# MicroMod-Artemis-ProcessorBoard.net
KiCad netlist of a schematic drawn in EAGLE
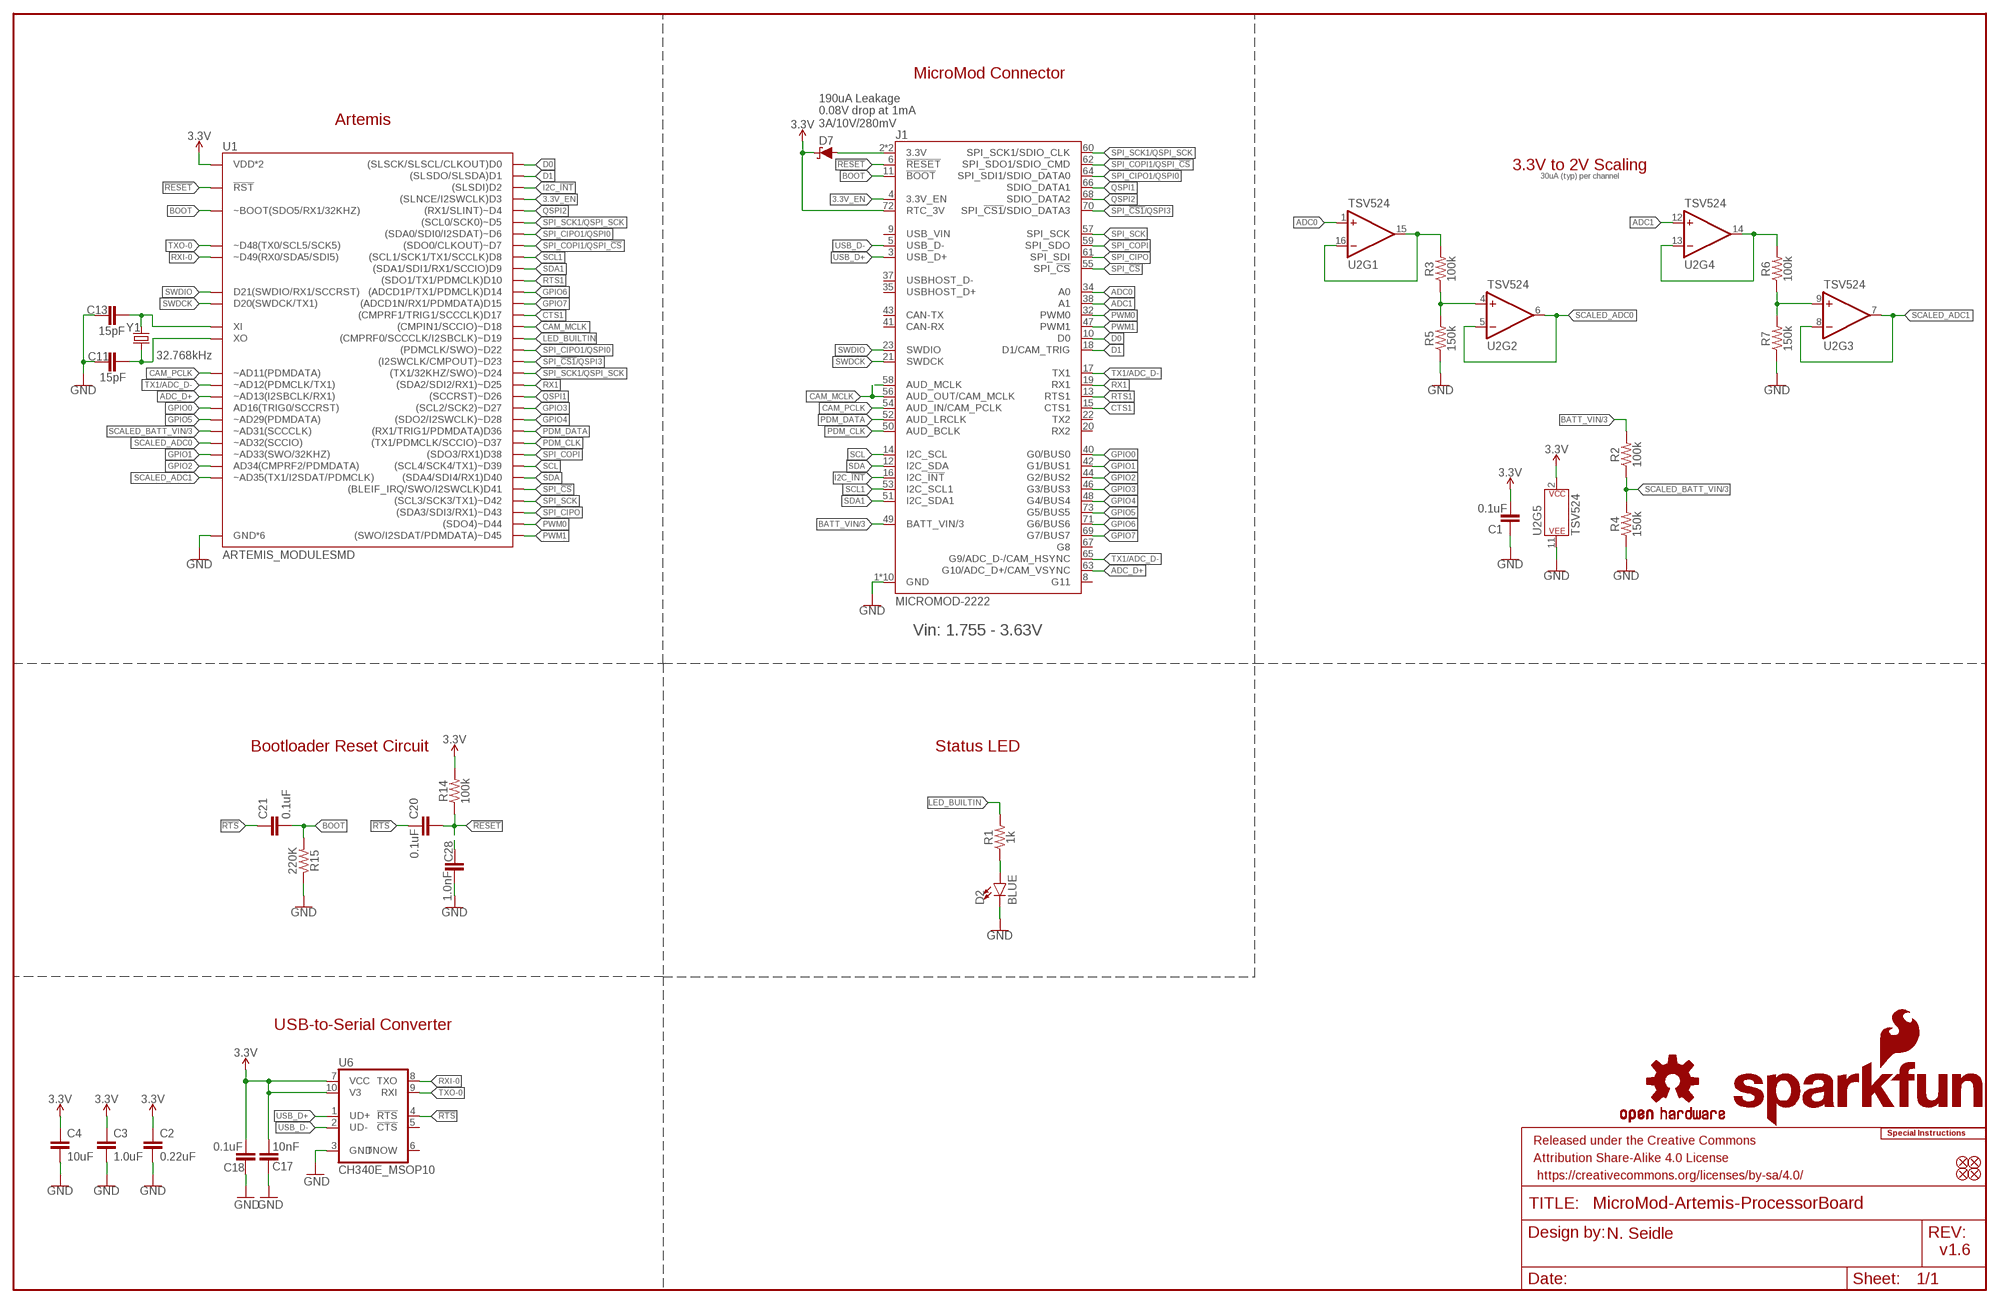
[diagram p0: schematic, sheet 1]

(export (version "E")
  (design (tool "Eeschema 10.0.6"))
  (components
    (comp (ref "C1")
      (value "0.1uF")
      (footprint "eagle-import:0402-TIGHT")
      (libsource (lib "eagle-import") (part "0.1UF-0402T-16V-10%"))
    )
    (comp (ref "C2")
      (value "0.22uF")
      (footprint "eagle-import:0402-TIGHT")
      (libsource (lib "eagle-import") (part "0.22UF-0402T-10V-10%"))
    )
    (comp (ref "C3")
      (value "1.0uF")
      (footprint "eagle-import:0402-TIGHT")
      (libsource (lib "eagle-import") (part "1.0UF-0402T-16V-10%"))
    )
    (comp (ref "C4")
      (value "10uF")
      (footprint "eagle-import:0603")
      (libsource (lib "eagle-import") (part "10UF-0603-6.3V-20%"))
    )
    (comp (ref "C11")
      (value "15pF")
      (footprint "eagle-import:0402-TIGHT")
      (libsource (lib "eagle-import") (part "15PF-0402T-50V-5%"))
    )
    (comp (ref "C13")
      (value "15pF")
      (footprint "eagle-import:0402-TIGHT")
      (libsource (lib "eagle-import") (part "15PF-0402T-50V-5%"))
    )
    (comp (ref "C17")
      (value "10nF")
      (footprint "eagle-import:0402-TIGHT")
      (libsource (lib "eagle-import") (part "10NF-0402T-25V-10%"))
    )
    (comp (ref "C18")
      (value "0.1uF")
      (footprint "eagle-import:0402-TIGHT")
      (libsource (lib "eagle-import") (part "0.1UF-0402T-16V-10%"))
    )
    (comp (ref "C20")
      (value "0.1uF")
      (footprint "eagle-import:0402-TIGHT")
      (libsource (lib "eagle-import") (part "0.1UF-0402T-16V-10%"))
    )
    (comp (ref "C21")
      (value "0.1uF")
      (footprint "eagle-import:0402-TIGHT")
      (libsource (lib "eagle-import") (part "0.1UF-0402T-16V-10%"))
    )
    (comp (ref "C28")
      (value "1.0nF")
      (footprint "eagle-import:0402-TIGHT")
      (libsource (lib "eagle-import") (part "1.0NF/1000PF-0402_TIGHT-50V-10%"))
    )
    (comp (ref "D2")
      (value "BLUE")
      (footprint "eagle-import:LED-0603")
      (libsource (lib "eagle-import") (part "LED-BLUE0603"))
    )
    (comp (ref "D7")
      (value "3A/10V/280mV")
      (footprint "eagle-import:SOD-323")
      (libsource (lib "eagle-import") (part "DIODE-SCHOTTKY-BAT60A"))
    )
    (comp (ref "FD1")
      (value "FIDUCIALUFIDUCIAL")
      (footprint "eagle-import:FIDUCIAL-MICRO")
      (libsource (lib "eagle-import") (part "FIDUCIALUFIDUCIAL"))
    )
    (comp (ref "FD2")
      (value "FIDUCIALUFIDUCIAL")
      (footprint "eagle-import:FIDUCIAL-MICRO")
      (libsource (lib "eagle-import") (part "FIDUCIALUFIDUCIAL"))
    )
    (comp (ref "FD3")
      (value "FIDUCIALUFIDUCIAL")
      (footprint "eagle-import:FIDUCIAL-MICRO")
      (libsource (lib "eagle-import") (part "FIDUCIALUFIDUCIAL"))
    )
    (comp (ref "FD4")
      (value "FIDUCIALUFIDUCIAL")
      (footprint "eagle-import:FIDUCIAL-MICRO")
      (libsource (lib "eagle-import") (part "FIDUCIALUFIDUCIAL"))
    )
    (comp (ref "FRAME1")
      (value "FRAME-LEDGER")
      (footprint "eagle-import:CREATIVE_COMMONS")
      (libsource (lib "eagle-import") (part "FRAME-LEDGER"))
    )
    (comp (ref "J1")
      (value "MICROMOD-2222")
      (footprint "eagle-import:M.2-CARD-E-22")
      (libsource (lib "eagle-import") (part "MICROMOD-2222"))
    )
    (comp (ref "LOGO1")
      (value "SFE_LOGO_NAME_FLAME.1_INCH")
      (footprint "eagle-import:SFE_LOGO_NAME_FLAME_.1")
      (libsource (lib "eagle-import") (part "SFE_LOGO_NAME_FLAME.1_INCH"))
    )
    (comp (ref "LOGO2")
      (value "SFE_LOGO_FLAME.1_INCH")
      (footprint "eagle-import:SFE_LOGO_FLAME_.1")
      (libsource (lib "eagle-import") (part "SFE_LOGO_FLAME.1_INCH"))
    )
    (comp (ref "LOGO3")
      (value "OSHW-LOGOMINI")
      (footprint "eagle-import:OSHW-LOGO-MINI")
      (libsource (lib "eagle-import") (part "OSHW-LOGOMINI"))
    )
    (comp (ref "LOGO4")
      (value "SPECIAL_INSTRUCTIONS-ORDERING")
      (footprint "eagle-import:ORDERING_INSTRUCTIONS")
      (libsource (lib "eagle-import") (part "SPECIAL_INSTRUCTIONS-ORDERING"))
    )
    (comp (ref "R1")
      (value "1k")
      (footprint "eagle-import:0402-TIGHT")
      (libsource (lib "eagle-import") (part "1KOHM-0402T-1/16W-1%"))
    )
    (comp (ref "R2")
      (value "100k")
      (footprint "eagle-import:0402-TIGHT")
      (libsource (lib "eagle-import") (part "100KOHM-0402T-1/16W-1%"))
    )
    (comp (ref "R3")
      (value "100k")
      (footprint "eagle-import:0402-TIGHT")
      (libsource (lib "eagle-import") (part "100KOHM-0402T-1/16W-1%"))
    )
    (comp (ref "R4")
      (value "150k")
      (footprint "eagle-import:0402-TIGHT")
      (libsource (lib "eagle-import") (part "150KOHM-0402T-1/16W-1%"))
    )
    (comp (ref "R5")
      (value "150k")
      (footprint "eagle-import:0402-TIGHT")
      (libsource (lib "eagle-import") (part "150KOHM-0402T-1/16W-1%"))
    )
    (comp (ref "R6")
      (value "100k")
      (footprint "eagle-import:0402-TIGHT")
      (libsource (lib "eagle-import") (part "100KOHM-0402T-1/16W-1%"))
    )
    (comp (ref "R7")
      (value "150k")
      (footprint "eagle-import:0402-TIGHT")
      (libsource (lib "eagle-import") (part "150KOHM-0402T-1/16W-1%"))
    )
    (comp (ref "R14")
      (value "100k")
      (footprint "eagle-import:0402-TIGHT")
      (libsource (lib "eagle-import") (part "100KOHM-0402T-1/16W-1%"))
    )
    (comp (ref "R15")
      (value "220K")
      (footprint "eagle-import:0402-TIGHT")
      (libsource (lib "eagle-import") (part "220KOHM-0402T-1/16W-1%"))
    )
    (comp (ref "U1")
      (value "ARTEMIS_MODULESMD")
      (footprint "eagle-import:ARTEMIS_FP")
      (libsource (lib "eagle-import") (part "ARTEMIS_MODULESMD"))
    )
    (comp (ref "U2")
      (value "TSV524")
      (footprint "eagle-import:QFN-16")
      (libsource (lib "eagle-import") (part "TSV524"))
    )
    (comp (ref "U6")
      (value "CH340E_MSOP10")
      (footprint "eagle-import:MSOP10")
      (libsource (lib "eagle-import") (part "CH340E_MSOP10"))
    )
    (comp (ref "Y1")
      (value "32.768kHz")
      (footprint "eagle-import:CRYSTAL-SMD-3.2X1.5MM")
      (libsource (lib "eagle-import") (part "CRYSTAL-32.768KHZSMD-3.2X1.5"))
    )
  )
  (nets
    (net (code "1") (name "/I2C_~{INT}") (class "Default")
      (node (ref "J1") (pin "16") (pinfunction "I2C_~{INT}_16") (pintype "bidirectional"))
      (node (ref "U1") (pin "D2") (pinfunction "(SLSDI)D2_D2") (pintype "bidirectional"))
    )
    (net (code "2") (name "/SPI_COPI1{slash}QSPI_~{CS}") (class "Default")
      (node (ref "J1") (pin "62") (pinfunction "SPI_SDO1/SDIO_CMD_62") (pintype "bidirectional"))
      (node (ref "U1") (pin "D7") (pinfunction "(SDO0/CLKOUT)~{D7}_D7") (pintype "bidirectional"))
    )
    (net (code "3") (name "/SPI_~{CS1}{slash}QSPI3") (class "Default")
      (node (ref "J1") (pin "70") (pinfunction "SPI_~{CS1}/SDIO_DATA3_70") (pintype "bidirectional"))
      (node (ref "U1") (pin "~D23") (pinfunction "(I2SWCLK/CMPOUT)~{D23}_~D23") (pintype "bidirectional"))
    )
    (net (code "4") (name "/SPI_~{CS}") (class "Default")
      (node (ref "J1") (pin "55") (pinfunction "SPI_~{CS}_55") (pintype "bidirectional"))
      (node (ref "U1") (pin "D41") (pinfunction "(BLEIF_IRQ/SWO/I2SWCLK)D41_D41") (pintype "bidirectional"))
    )
    (net (code "5") (name "/~{RESET}") (class "Default")
      (node (ref "C20") (pin "2") (pinfunction "2_2") (pintype "passive"))
      (node (ref "C28") (pin "1") (pinfunction "1_1") (pintype "passive"))
      (node (ref "J1") (pin "6") (pinfunction "~{RESET}_6") (pintype "bidirectional"))
      (node (ref "R14") (pin "1") (pinfunction "1_1") (pintype "passive"))
      (node (ref "U1") (pin "~RST") (pinfunction "~{RST}_~RST") (pintype "bidirectional"))
    )
    (net (code "6") (name "/~{RTS}") (class "Default")
      (node (ref "C20") (pin "1") (pinfunction "1_1") (pintype "passive"))
      (node (ref "C21") (pin "1") (pinfunction "1_1") (pintype "passive"))
      (node (ref "U6") (pin "4") (pinfunction "~{RTS}_4") (pintype "bidirectional"))
    )
    (net (code "7") (name "3.3V") (class "Default")
      (node (ref "C1") (pin "1") (pinfunction "1_1") (pintype "passive"))
      (node (ref "C17") (pin "1") (pinfunction "1_1") (pintype "passive"))
      (node (ref "C18") (pin "1") (pinfunction "1_1") (pintype "passive"))
      (node (ref "C2") (pin "1") (pinfunction "1_1") (pintype "passive"))
      (node (ref "C3") (pin "1") (pinfunction "1_1") (pintype "passive"))
      (node (ref "C4") (pin "1") (pinfunction "1_1") (pintype "passive"))
      (node (ref "D7") (pin "C") (pinfunction "C_C") (pintype "passive"))
      (node (ref "J1") (pin "72") (pinfunction "RTC_3V_72") (pintype "bidirectional"))
      (node (ref "R14") (pin "2") (pinfunction "2_2") (pintype "passive"))
      (node (ref "U1") (pin "VDD@36") (pinfunction "VDD*2_VDD@36") (pintype "bidirectional"))
      (node (ref "U1") (pin "VDD@37") (pinfunction "VDD*2_VDD@37") (pintype "bidirectional"))
      (node (ref "U2") (pin "2") (pinfunction "V+_2") (pintype "bidirectional"))
      (node (ref "U6") (pin "10") (pinfunction "V3_10") (pintype "bidirectional"))
      (node (ref "U6") (pin "7") (pinfunction "VCC_7") (pintype "bidirectional"))
    )
    (net (code "8") (name "3.3V_EN") (class "Default")
      (node (ref "J1") (pin "4") (pinfunction "3.3V_EN_4") (pintype "bidirectional"))
      (node (ref "U1") (pin "D3") (pinfunction "(SLNCE/I2SWCLK)D3_D3") (pintype "bidirectional"))
    )
    (net (code "9") (name "ADC0") (class "Default")
      (node (ref "J1") (pin "34") (pinfunction "A0_34") (pintype "bidirectional"))
      (node (ref "U2") (pin "1") (pinfunction "+IN_1") (pintype "input"))
    )
    (net (code "10") (name "ADC1") (class "Default")
      (node (ref "J1") (pin "38") (pinfunction "A1_38") (pintype "bidirectional"))
      (node (ref "U2") (pin "12") (pinfunction "+IN_12") (pintype "input"))
    )
    (net (code "11") (name "ADC_D+") (class "Default")
      (node (ref "J1") (pin "63") (pinfunction "G10/ADC_D+/CAM_VSYNC_63") (pintype "bidirectional"))
      (node (ref "U1") (pin "~AD13") (pinfunction "~{AD13(I2SBCLK/RX1})_~AD13") (pintype "bidirectional"))
    )
    (net (code "12") (name "BATT_VIN{slash}3") (class "Default")
      (node (ref "J1") (pin "49") (pinfunction "BATT_VIN/3_49") (pintype "bidirectional"))
      (node (ref "R2") (pin "2") (pinfunction "2_2") (pintype "passive"))
    )
    (net (code "13") (name "BOOT") (class "Default")
      (node (ref "C21") (pin "2") (pinfunction "2_2") (pintype "passive"))
      (node (ref "J1") (pin "11") (pinfunction "~{BOOT}_11") (pintype "bidirectional"))
      (node (ref "R15") (pin "2") (pinfunction "2_2") (pintype "passive"))
      (node (ref "U1") (pin "BOOT") (pinfunction "~{BOOT(SDO5/RX1/32KHZ})_BOOT") (pintype "bidirectional"))
    )
    (net (code "14") (name "CAM_MCLK") (class "Default")
      (node (ref "J1") (pin "56") (pinfunction "AUD_OUT/CAM_MCLK_56") (pintype "bidirectional"))
      (node (ref "J1") (pin "58") (pinfunction "AUD_MCLK_58") (pintype "bidirectional"))
      (node (ref "U1") (pin "~D18") (pinfunction "(CMPIN1/SCCIO)~{D18}_~D18") (pintype "bidirectional"))
    )
    (net (code "15") (name "CAM_PCLK") (class "Default")
      (node (ref "J1") (pin "54") (pinfunction "AUD_IN/CAM_PCLK_54") (pintype "bidirectional"))
      (node (ref "U1") (pin "~AD11") (pinfunction "~{AD11(PDMDATA})_~AD11") (pintype "bidirectional"))
    )
    (net (code "16") (name "CTS1") (class "Default")
      (node (ref "J1") (pin "15") (pinfunction "CTS1_15") (pintype "bidirectional"))
      (node (ref "U1") (pin "D17") (pinfunction "(CMPRF1/TRIG1/SCCCLK)D17_D17") (pintype "bidirectional"))
    )
    (net (code "17") (name "D0") (class "Default")
      (node (ref "J1") (pin "10") (pinfunction "D0_10") (pintype "bidirectional"))
      (node (ref "U1") (pin "D0") (pinfunction "(SLSCK/SLSCL/CLKOUT)D0_D0") (pintype "bidirectional"))
    )
    (net (code "18") (name "D1") (class "Default")
      (node (ref "J1") (pin "18") (pinfunction "D1/CAM_TRIG_18") (pintype "bidirectional"))
      (node (ref "U1") (pin "D1") (pinfunction "(SLSDO/SLSDA)D1_D1") (pintype "bidirectional"))
    )
    (net (code "19") (name "GND") (class "Default")
      (node (ref "C1") (pin "2") (pinfunction "2_2") (pintype "passive"))
      (node (ref "C11") (pin "1") (pinfunction "1_1") (pintype "passive"))
      (node (ref "C13") (pin "1") (pinfunction "1_1") (pintype "passive"))
      (node (ref "C17") (pin "2") (pinfunction "2_2") (pintype "passive"))
      (node (ref "C18") (pin "2") (pinfunction "2_2") (pintype "passive"))
      (node (ref "C2") (pin "2") (pinfunction "2_2") (pintype "passive"))
      (node (ref "C28") (pin "2") (pinfunction "2_2") (pintype "passive"))
      (node (ref "C3") (pin "2") (pinfunction "2_2") (pintype "passive"))
      (node (ref "C4") (pin "2") (pinfunction "2_2") (pintype "passive"))
      (node (ref "D2") (pin "C") (pinfunction "C_C") (pintype "passive"))
      (node (ref "J1") (pin "1") (pinfunction "GND_1") (pintype "bidirectional"))
      (node (ref "J1") (pin "33") (pinfunction "GND_33") (pintype "bidirectional"))
      (node (ref "J1") (pin "36") (pinfunction "GND_36") (pintype "bidirectional"))
      (node (ref "J1") (pin "39") (pinfunction "GND_39") (pintype "bidirectional"))
      (node (ref "J1") (pin "45") (pinfunction "GND_45") (pintype "bidirectional"))
      (node (ref "J1") (pin "7") (pinfunction "GND_7") (pintype "bidirectional"))
      (node (ref "J1") (pin "75") (pinfunction "GND_75") (pintype "bidirectional"))
      (node (ref "J1") (pin "GND1") (pinfunction "GND_GND1") (pintype "bidirectional"))
      (node (ref "J1") (pin "GND2") (pinfunction "GND_GND2") (pintype "bidirectional"))
      (node (ref "J1") (pin "GND3") (pinfunction "GND_GND3") (pintype "bidirectional"))
      (node (ref "R15") (pin "1") (pinfunction "1_1") (pintype "passive"))
      (node (ref "R4") (pin "1") (pinfunction "1_1") (pintype "passive"))
      (node (ref "R5") (pin "1") (pinfunction "1_1") (pintype "passive"))
      (node (ref "R7") (pin "1") (pinfunction "1_1") (pintype "passive"))
      (node (ref "U1") (pin "GND@1") (pinfunction "GND*6_GND@1") (pintype "bidirectional"))
      (node (ref "U1") (pin "GND@22") (pinfunction "GND*6_GND@22") (pintype "bidirectional"))
      (node (ref "U1") (pin "GND@38") (pinfunction "GND*6_GND@38") (pintype "bidirectional"))
      (node (ref "U1") (pin "GND@39") (pinfunction "GND*6_GND@39") (pintype "bidirectional"))
      (node (ref "U1") (pin "GND@47") (pinfunction "GND*6_GND@47") (pintype "bidirectional"))
      (node (ref "U1") (pin "GND@59") (pinfunction "GND*6_GND@59") (pintype "bidirectional"))
      (node (ref "U2") (pin "11") (pinfunction "V-_11") (pintype "bidirectional"))
      (node (ref "U6") (pin "3") (pinfunction "GND_3") (pintype "bidirectional"))
    )
    (net (code "20") (name "GPIO0") (class "Default")
      (node (ref "J1") (pin "40") (pinfunction "G0/BUS0_40") (pintype "bidirectional"))
      (node (ref "U1") (pin "AD16") (pinfunction "AD16(TRIG0/SCCRST)_AD16") (pintype "bidirectional"))
    )
    (net (code "21") (name "GPIO1") (class "Default")
      (node (ref "J1") (pin "42") (pinfunction "G1/BUS1_42") (pintype "bidirectional"))
      (node (ref "U1") (pin "~AD33/SWO") (pinfunction "~{AD33(SWO/32KHZ})_~AD33/SWO") (pintype "bidirectional"))
    )
    (net (code "22") (name "GPIO2") (class "Default")
      (node (ref "J1") (pin "44") (pinfunction "G2/BUS2_44") (pintype "bidirectional"))
      (node (ref "U1") (pin "AD34") (pinfunction "AD34(CMPRF2/PDMDATA)_AD34") (pintype "bidirectional"))
    )
    (net (code "23") (name "GPIO3") (class "Default")
      (node (ref "J1") (pin "46") (pinfunction "G3/BUS3_46") (pintype "bidirectional"))
      (node (ref "U1") (pin "~D27") (pinfunction "(SCL2/SCK2)~{D27}_~D27") (pintype "bidirectional"))
    )
    (net (code "24") (name "GPIO4") (class "Default")
      (node (ref "J1") (pin "48") (pinfunction "G4/BUS4_48") (pintype "bidirectional"))
      (node (ref "U1") (pin "~D28") (pinfunction "(SDO2/I2SWCLK)~{D28}_~D28") (pintype "bidirectional"))
    )
    (net (code "25") (name "GPIO5") (class "Default")
      (node (ref "J1") (pin "73") (pinfunction "G5/BUS5_73") (pintype "bidirectional"))
      (node (ref "U1") (pin "~AD29") (pinfunction "~{AD29(PDMDATA})_~AD29") (pintype "bidirectional"))
    )
    (net (code "26") (name "GPIO6") (class "Default")
      (node (ref "J1") (pin "71") (pinfunction "G6/BUS6_71") (pintype "bidirectional"))
      (node (ref "U1") (pin "D14") (pinfunction "(ADCD1P/TX1/PDMCLK)D14_D14") (pintype "bidirectional"))
    )
    (net (code "27") (name "GPIO7") (class "Default")
      (node (ref "J1") (pin "69") (pinfunction "G7/BUS7_69") (pintype "bidirectional"))
      (node (ref "U1") (pin "D15") (pinfunction "(ADCD1N/RX1/PDMDATA)D15_D15") (pintype "bidirectional"))
    )
    (net (code "28") (name "LED_BUILTIN") (class "Default")
      (node (ref "R1") (pin "2") (pinfunction "2_2") (pintype "passive"))
      (node (ref "U1") (pin "~D19") (pinfunction "(CMPRF0/SCCCLK/I2SBCLK)~{D19}_~D19") (pintype "bidirectional"))
    )
    (net (code "29") (name "Net-(D2-PadA)") (class "Default")
      (node (ref "D2") (pin "A") (pinfunction "A_A") (pintype "passive"))
      (node (ref "R1") (pin "1") (pinfunction "1_1") (pintype "passive"))
    )
    (net (code "30") (name "Net-(D7-PadA)") (class "Default")
      (node (ref "D7") (pin "A") (pinfunction "A_A") (pintype "passive"))
      (node (ref "J1") (pin "2") (pinfunction "3.3V_2") (pintype "bidirectional"))
      (node (ref "J1") (pin "74") (pinfunction "3.3V_74") (pintype "bidirectional"))
    )
    (net (code "31") (name "Net-(U2A--IN)") (class "Default")
      (node (ref "R3") (pin "2") (pinfunction "2_2") (pintype "passive"))
      (node (ref "U2") (pin "15") (pinfunction "OUT_15") (pintype "output"))
      (node (ref "U2") (pin "16") (pinfunction "-IN_16") (pintype "input"))
    )
    (net (code "32") (name "Net-(U2B-+IN)") (class "Default")
      (node (ref "R3") (pin "1") (pinfunction "1_1") (pintype "passive"))
      (node (ref "R5") (pin "2") (pinfunction "2_2") (pintype "passive"))
      (node (ref "U2") (pin "4") (pinfunction "+IN_4") (pintype "input"))
    )
    (net (code "33") (name "Net-(U2C-+IN)") (class "Default")
      (node (ref "R6") (pin "1") (pinfunction "1_1") (pintype "passive"))
      (node (ref "R7") (pin "2") (pinfunction "2_2") (pintype "passive"))
      (node (ref "U2") (pin "9") (pinfunction "+IN_9") (pintype "input"))
    )
    (net (code "34") (name "Net-(U2D--IN)") (class "Default")
      (node (ref "R6") (pin "2") (pinfunction "2_2") (pintype "passive"))
      (node (ref "U2") (pin "13") (pinfunction "-IN_13") (pintype "input"))
      (node (ref "U2") (pin "14") (pinfunction "OUT_14") (pintype "output"))
    )
    (net (code "35") (name "Net-(Y1-1)") (class "Default")
      (node (ref "C13") (pin "2") (pinfunction "2_2") (pintype "passive"))
      (node (ref "U1") (pin "XI") (pinfunction "XI_XI") (pintype "bidirectional"))
      (node (ref "Y1") (pin "P$1") (pinfunction "1_P$1") (pintype "passive"))
    )
    (net (code "36") (name "Net-(Y1-2)") (class "Default")
      (node (ref "C11") (pin "2") (pinfunction "2_2") (pintype "passive"))
      (node (ref "U1") (pin "XO") (pinfunction "XO_XO") (pintype "bidirectional"))
      (node (ref "Y1") (pin "P$2") (pinfunction "2_P$2") (pintype "passive"))
    )
    (net (code "37") (name "PDM_CLK") (class "Default")
      (node (ref "J1") (pin "50") (pinfunction "AUD_BCLK_50") (pintype "bidirectional"))
      (node (ref "U1") (pin "~D37") (pinfunction "(TX1/PDMCLK/SCCIO)~{D37}_~D37") (pintype "bidirectional"))
    )
    (net (code "38") (name "PDM_DATA") (class "Default")
      (node (ref "J1") (pin "52") (pinfunction "AUD_LRCLK_52") (pintype "bidirectional"))
      (node (ref "U1") (pin "D36") (pinfunction "(RX1/TRIG1/PDMDATA)D36_D36") (pintype "bidirectional"))
    )
    (net (code "39") (name "PWM0") (class "Default")
      (node (ref "J1") (pin "32") (pinfunction "PWM0_32") (pintype "bidirectional"))
      (node (ref "U1") (pin "~D44") (pinfunction "(SDO4)~{D44}_~D44") (pintype "bidirectional"))
    )
    (net (code "40") (name "PWM1") (class "Default")
      (node (ref "J1") (pin "47") (pinfunction "PWM1_47") (pintype "bidirectional"))
      (node (ref "U1") (pin "~D45") (pinfunction "(SWO/I2SDAT/PDMDATA)~{D45}_~D45") (pintype "bidirectional"))
    )
    (net (code "41") (name "QSPI1") (class "Default")
      (node (ref "J1") (pin "66") (pinfunction "SDIO_DATA1_66") (pintype "bidirectional"))
      (node (ref "U1") (pin "~D26") (pinfunction "(SCCRST)~{D26}_~D26") (pintype "bidirectional"))
    )
    (net (code "42") (name "QSPI2") (class "Default")
      (node (ref "J1") (pin "68") (pinfunction "SDIO_DATA2_68") (pintype "bidirectional"))
      (node (ref "U1") (pin "~D4") (pinfunction "(RX1/SLINT)~{D4}_~D4") (pintype "bidirectional"))
    )
    (net (code "43") (name "RTS1") (class "Default")
      (node (ref "J1") (pin "13") (pinfunction "RTS1_13") (pintype "bidirectional"))
      (node (ref "U1") (pin "D10") (pinfunction "(SDO1/TX1/PDMCLK)D10_D10") (pintype "bidirectional"))
    )
    (net (code "44") (name "RX1") (class "Default")
      (node (ref "J1") (pin "19") (pinfunction "RX1_19") (pintype "bidirectional"))
      (node (ref "U1") (pin "~D25") (pinfunction "(SDA2/SDI2/RX1)~{D25}_~D25") (pintype "bidirectional"))
    )
    (net (code "45") (name "RXI-0") (class "Default")
      (node (ref "U1") (pin "RXI-0") (pinfunction "~{D49(RX0/SDA5/SDI5})_RXI-0") (pintype "bidirectional"))
      (node (ref "U6") (pin "8") (pinfunction "TXO_8") (pintype "bidirectional"))
    )
    (net (code "46") (name "SCALED_ADC0") (class "Default")
      (node (ref "U1") (pin "~AD32") (pinfunction "~{AD32(SCCIO})_~AD32") (pintype "bidirectional"))
      (node (ref "U2") (pin "5") (pinfunction "-IN_5") (pintype "input"))
      (node (ref "U2") (pin "6") (pinfunction "OUT_6") (pintype "output"))
    )
    (net (code "47") (name "SCALED_ADC1") (class "Default")
      (node (ref "U1") (pin "~AD35") (pinfunction "~{AD35(TX1/I2SDAT/PDMCLK})_~AD35") (pintype "bidirectional"))
      (node (ref "U2") (pin "7") (pinfunction "OUT_7") (pintype "output"))
      (node (ref "U2") (pin "8") (pinfunction "-IN_8") (pintype "input"))
    )
    (net (code "48") (name "SCALED_BATT_VIN{slash}3") (class "Default")
      (node (ref "R2") (pin "1") (pinfunction "1_1") (pintype "passive"))
      (node (ref "R4") (pin "2") (pinfunction "2_2") (pintype "passive"))
      (node (ref "U1") (pin "~AD31") (pinfunction "~{AD31(SCCCLK})_~AD31") (pintype "bidirectional"))
    )
    (net (code "49") (name "SCL") (class "Default")
      (node (ref "J1") (pin "14") (pinfunction "I2C_SCL_14") (pintype "bidirectional"))
      (node (ref "U1") (pin "~D39") (pinfunction "(SCL4/SCK4/TX1)~{D39}_~D39") (pintype "bidirectional"))
    )
    (net (code "50") (name "SCL1") (class "Default")
      (node (ref "J1") (pin "53") (pinfunction "I2C_SCL1_53") (pintype "bidirectional"))
      (node (ref "U1") (pin "D8") (pinfunction "(SCL1/SCK1/TX1/SCCLK)D8_D8") (pintype "bidirectional"))
    )
    (net (code "51") (name "SDA") (class "Default")
      (node (ref "J1") (pin "12") (pinfunction "I2C_SDA_12") (pintype "bidirectional"))
      (node (ref "U1") (pin "D40") (pinfunction "(SDA4/SDI4/RX1)D40_D40") (pintype "bidirectional"))
    )
    (net (code "52") (name "SDA1") (class "Default")
      (node (ref "J1") (pin "51") (pinfunction "I2C_SDA1_51") (pintype "bidirectional"))
      (node (ref "U1") (pin "D9") (pinfunction "(SDA1/SDI1/RX1/SCCIO)D9_D9") (pintype "bidirectional"))
    )
    (net (code "53") (name "SPI_CIPO") (class "Default")
      (node (ref "J1") (pin "61") (pinfunction "SPI_SDI_61") (pintype "bidirectional"))
      (node (ref "U1") (pin "~D43") (pinfunction "(SDA3/SDI3/RX1)~{D43}_~D43") (pintype "bidirectional"))
    )
    (net (code "54") (name "SPI_CIPO1{slash}QSPI0") (class "Default")
      (node (ref "J1") (pin "64") (pinfunction "SPI_SDI1/SDIO_DATA0_64") (pintype "bidirectional"))
      (node (ref "U1") (pin "~D22") (pinfunction "(PDMCLK/SWO)~{D22}_~D22") (pintype "bidirectional"))
      (node (ref "U1") (pin "~D6") (pinfunction "(SDA0/SDI0/I2SDAT)~{D6}_~D6") (pintype "bidirectional"))
    )
    (net (code "55") (name "SPI_COPI") (class "Default")
      (node (ref "J1") (pin "59") (pinfunction "SPI_SDO_59") (pintype "bidirectional"))
      (node (ref "U1") (pin "D38") (pinfunction "(SDO3/RX1)D38_D38") (pintype "bidirectional"))
    )
    (net (code "56") (name "SPI_SCK") (class "Default")
      (node (ref "J1") (pin "57") (pinfunction "SPI_SCK_57") (pintype "bidirectional"))
      (node (ref "U1") (pin "~D42") (pinfunction "(SCL3/SCK3/TX1)~{D42}_~D42") (pintype "bidirectional"))
    )
    (net (code "57") (name "SPI_SCK1{slash}QSPI_SCK") (class "Default")
      (node (ref "J1") (pin "60") (pinfunction "SPI_SCK1/SDIO_CLK_60") (pintype "bidirectional"))
      (node (ref "U1") (pin "~D24") (pinfunction "(TX1/32KHZ/SWO)~{D24}_~D24") (pintype "bidirectional"))
      (node (ref "U1") (pin "~D5") (pinfunction "(SCL0/SCK0)~{D5}_~D5") (pintype "bidirectional"))
    )
    (net (code "58") (name "SWDCK") (class "Default")
      (node (ref "J1") (pin "21") (pinfunction "SWDCK_21") (pintype "bidirectional"))
      (node (ref "U1") (pin "SWDCK") (pinfunction "D20(SWDCK/TX1)_SWDCK") (pintype "bidirectional"))
    )
    (net (code "59") (name "SWDIO") (class "Default")
      (node (ref "J1") (pin "23") (pinfunction "SWDIO_23") (pintype "bidirectional"))
      (node (ref "U1") (pin "SWDIO") (pinfunction "D21(SWDIO/RX1/SCCRST)_SWDIO") (pintype "bidirectional"))
    )
    (net (code "60") (name "TX1{slash}ADC_D-") (class "Default")
      (node (ref "J1") (pin "17") (pinfunction "TX1_17") (pintype "bidirectional"))
      (node (ref "J1") (pin "65") (pinfunction "G9/ADC_D-/CAM_HSYNC_65") (pintype "bidirectional"))
      (node (ref "U1") (pin "~AD12") (pinfunction "~{AD12(PDMCLK/TX1})_~AD12") (pintype "bidirectional"))
    )
    (net (code "61") (name "TXO-0") (class "Default")
      (node (ref "U1") (pin "TXO-0") (pinfunction "~{D48(TX0/SCL5/SCK5})_TXO-0") (pintype "bidirectional"))
      (node (ref "U6") (pin "9") (pinfunction "RXI_9") (pintype "bidirectional"))
    )
    (net (code "62") (name "USB_D+") (class "Default")
      (node (ref "J1") (pin "3") (pinfunction "USB_D+_3") (pintype "bidirectional"))
      (node (ref "U6") (pin "1") (pinfunction "UD+_1") (pintype "bidirectional"))
    )
    (net (code "63") (name "USB_D-") (class "Default")
      (node (ref "J1") (pin "5") (pinfunction "USB_D-_5") (pintype "bidirectional"))
      (node (ref "U6") (pin "2") (pinfunction "UD-_2") (pintype "bidirectional"))
    )
    (net (code "64") (name "unconnected-(J1-CAN-RX-Pad41)") (class "Default")
      (node (ref "J1") (pin "41") (pinfunction "CAN-RX_41") (pintype "bidirectional"))
    )
    (net (code "65") (name "unconnected-(J1-CAN-TX-Pad43)") (class "Default")
      (node (ref "J1") (pin "43") (pinfunction "CAN-TX_43") (pintype "bidirectional"))
    )
    (net (code "66") (name "unconnected-(J1-G8-Pad67)") (class "Default")
      (node (ref "J1") (pin "67") (pinfunction "G8_67") (pintype "bidirectional"))
    )
    (net (code "67") (name "unconnected-(J1-G11-Pad8)") (class "Default")
      (node (ref "J1") (pin "8") (pinfunction "G11_8") (pintype "bidirectional"))
    )
    (net (code "68") (name "unconnected-(J1-RX2-Pad20)") (class "Default")
      (node (ref "J1") (pin "20") (pinfunction "RX2_20") (pintype "bidirectional"))
    )
    (net (code "69") (name "unconnected-(J1-TX2-Pad22)") (class "Default")
      (node (ref "J1") (pin "22") (pinfunction "TX2_22") (pintype "bidirectional"))
    )
    (net (code "70") (name "unconnected-(J1-USBHOST_D+-Pad35)") (class "Default")
      (node (ref "J1") (pin "35") (pinfunction "USBHOST_D+_35") (pintype "bidirectional"))
    )
    (net (code "71") (name "unconnected-(J1-USBHOST_D--Pad37)") (class "Default")
      (node (ref "J1") (pin "37") (pinfunction "USBHOST_D-_37") (pintype "bidirectional"))
    )
    (net (code "72") (name "unconnected-(J1-USB_VIN-Pad9)") (class "Default")
      (node (ref "J1") (pin "9") (pinfunction "USB_VIN_9") (pintype "bidirectional"))
    )
    (net (code "73") (name "unconnected-(U6-TNOW-Pad6)") (class "Default")
      (node (ref "U6") (pin "6") (pinfunction "TNOW_6") (pintype "bidirectional"))
    )
    (net (code "74") (name "unconnected-(U6-~{CTS}-Pad5)") (class "Default")
      (node (ref "U6") (pin "5") (pinfunction "~{CTS}_5") (pintype "bidirectional"))
    )
  )
)
